# improved-handheld-turbidimeter_power_dec.net
KiCad netlist of a schematic drawn in EAGLE
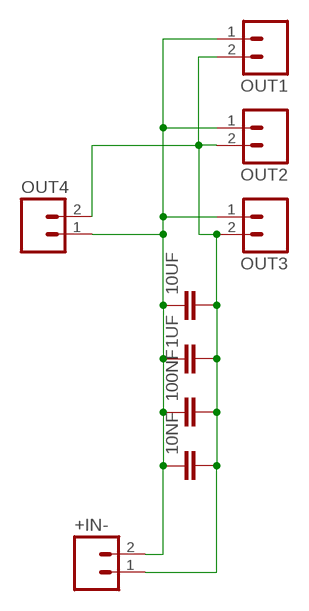
[diagram p0: schematic, sheet 1]

(export (version "E")
  (design (tool "Eeschema 10.0.6"))
  (components
    (comp (ref "+IN-")
      (value "M02PTH")
      (footprint "eagle-import:1X02")
      (libsource (lib "eagle-import") (part "M02PTH"))
    )
    (comp (ref "1UF")
      (value "CAP0805")
      (footprint "eagle-import:0805")
      (libsource (lib "eagle-import") (part "CAP0805"))
    )
    (comp (ref "10NF")
      (value "CAP0805")
      (footprint "eagle-import:0805")
      (libsource (lib "eagle-import") (part "CAP0805"))
    )
    (comp (ref "10UF")
      (value "CAP0805")
      (footprint "eagle-import:0805")
      (libsource (lib "eagle-import") (part "CAP0805"))
    )
    (comp (ref "100NF")
      (value "CAP0805")
      (footprint "eagle-import:0805")
      (libsource (lib "eagle-import") (part "CAP0805"))
    )
    (comp (ref "OUT1")
      (value "M02PTH")
      (footprint "eagle-import:1X02")
      (libsource (lib "eagle-import") (part "M02PTH"))
    )
    (comp (ref "OUT2")
      (value "M02PTH")
      (footprint "eagle-import:1X02")
      (libsource (lib "eagle-import") (part "M02PTH"))
    )
    (comp (ref "OUT3")
      (value "M02PTH")
      (footprint "eagle-import:1X02")
      (libsource (lib "eagle-import") (part "M02PTH"))
    )
    (comp (ref "OUT4")
      (value "M02PTH")
      (footprint "eagle-import:1X02")
      (libsource (lib "eagle-import") (part "M02PTH"))
    )
  )
  (nets
    (net (code "1") (name "Net-(+IN--Pad1)") (class "Default")
      (node (ref "+IN-") (pin "1") (pinfunction "1_1") (pintype "passive"))
      (node (ref "100NF") (pin "2") (pinfunction "2_2") (pintype "passive"))
      (node (ref "10NF") (pin "2") (pinfunction "2_2") (pintype "passive"))
      (node (ref "10UF") (pin "2") (pinfunction "2_2") (pintype "passive"))
      (node (ref "1UF") (pin "2") (pinfunction "2_2") (pintype "passive"))
      (node (ref "OUT1") (pin "2") (pinfunction "2_2") (pintype "passive"))
      (node (ref "OUT2") (pin "2") (pinfunction "2_2") (pintype "passive"))
      (node (ref "OUT3") (pin "2") (pinfunction "2_2") (pintype "passive"))
      (node (ref "OUT4") (pin "2") (pinfunction "2_2") (pintype "passive"))
    )
    (net (code "2") (name "Net-(+IN--Pad2)") (class "Default")
      (node (ref "+IN-") (pin "2") (pinfunction "2_2") (pintype "passive"))
      (node (ref "100NF") (pin "1") (pinfunction "1_1") (pintype "passive"))
      (node (ref "10NF") (pin "1") (pinfunction "1_1") (pintype "passive"))
      (node (ref "10UF") (pin "1") (pinfunction "1_1") (pintype "passive"))
      (node (ref "1UF") (pin "1") (pinfunction "1_1") (pintype "passive"))
      (node (ref "OUT1") (pin "1") (pinfunction "1_1") (pintype "passive"))
      (node (ref "OUT2") (pin "1") (pinfunction "1_1") (pintype "passive"))
      (node (ref "OUT3") (pin "1") (pinfunction "1_1") (pintype "passive"))
      (node (ref "OUT4") (pin "1") (pinfunction "1_1") (pintype "passive"))
    )
  )
)
